# mixer_board_input_and_mute_circuit.net
KiCad netlist of a schematic drawn in EAGLE
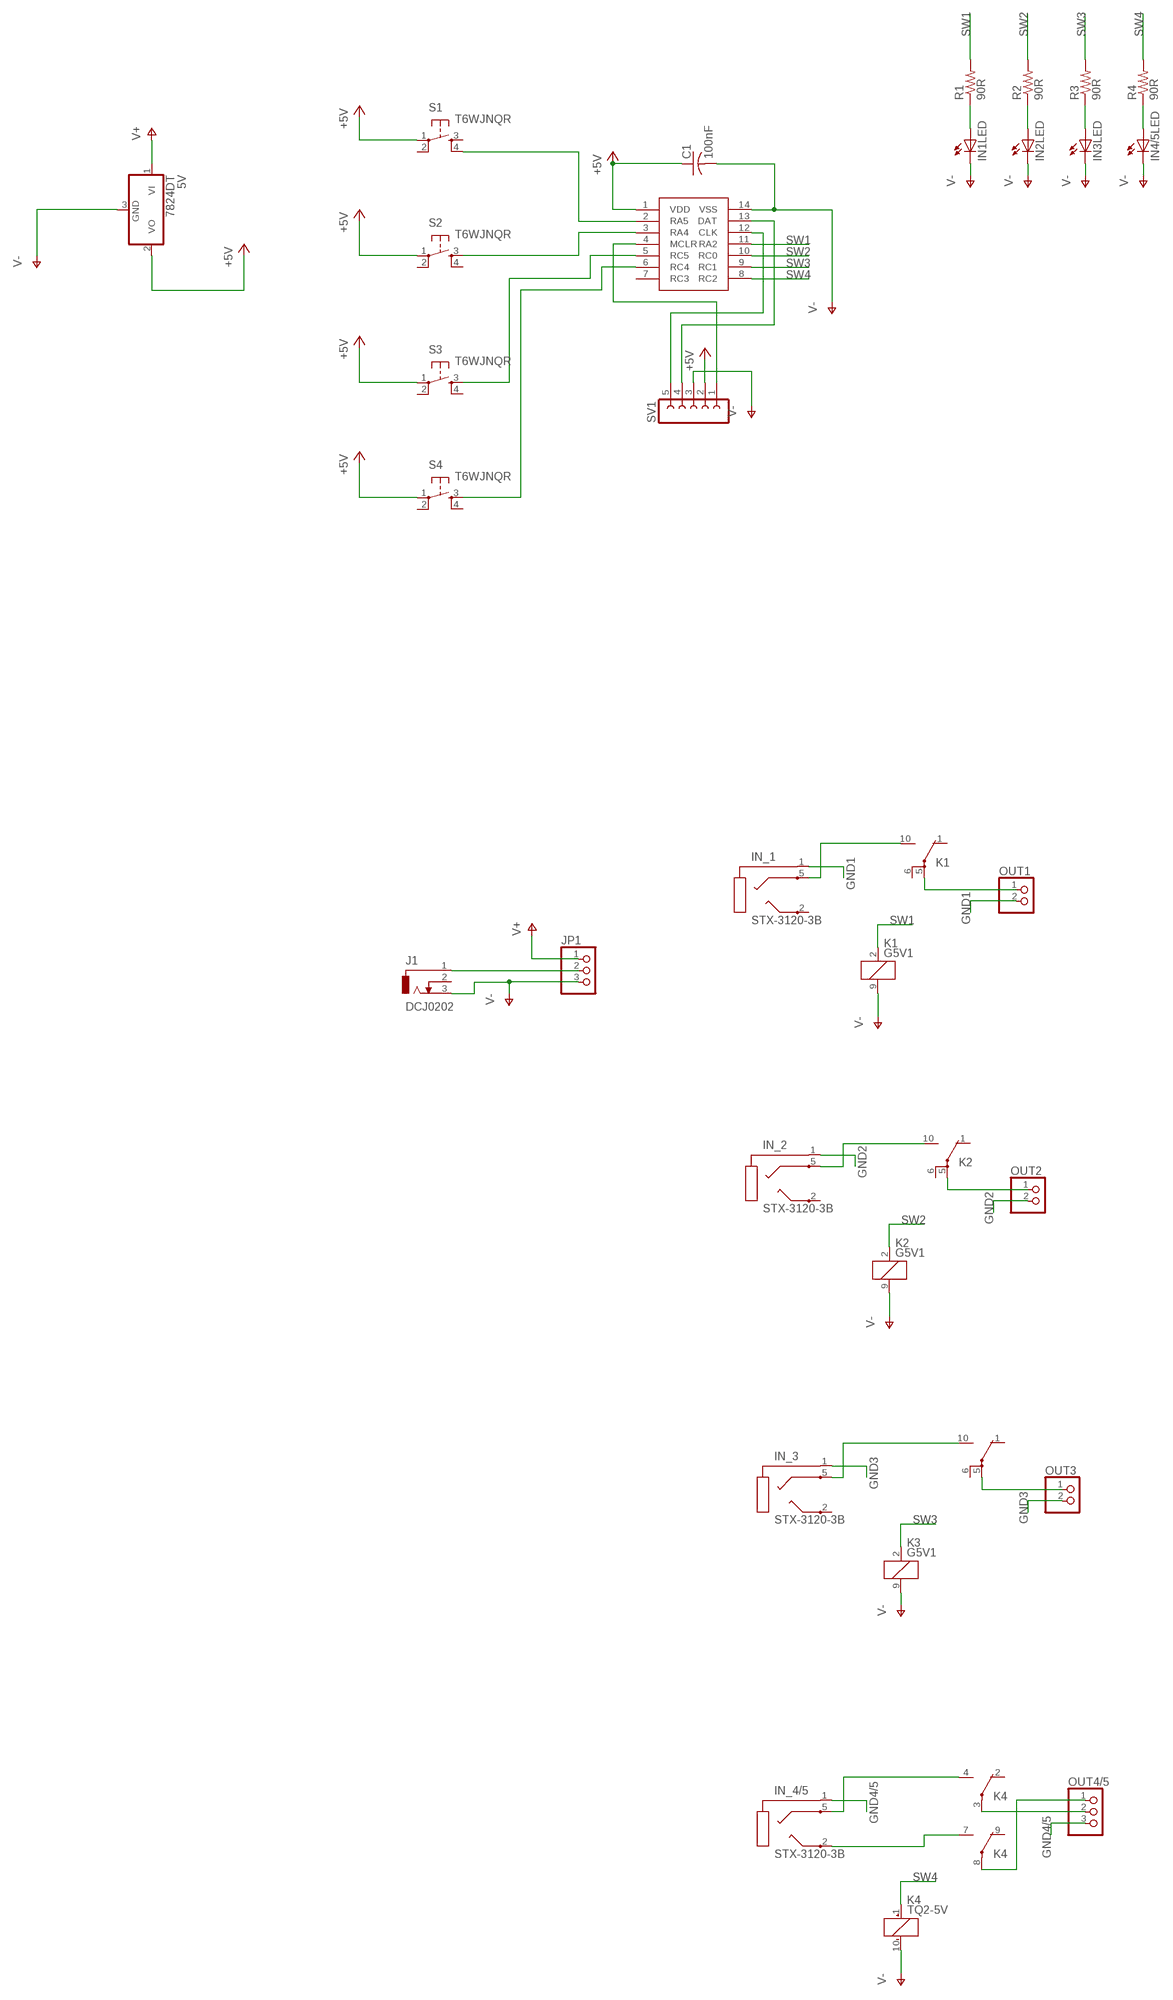
[diagram p0: schematic, sheet 1]

(export (version "E")
  (design (tool "Eeschema 10.0.6"))
  (components
    (comp (ref "5V")
      (value "7824DT")
      (footprint "eagle-import:TO252")
      (libsource (lib "eagle-import") (part "78DT24"))
    )
    (comp (ref "C1")
      (value "100nF")
      (footprint "eagle-import:C0805")
      (libsource (lib "eagle-import") (part "C-USC0805"))
    )
    (comp (ref "IN1LED")
      (value "LEDCHIPLED_1206")
      (footprint "eagle-import:CHIPLED_1206")
      (libsource (lib "eagle-import") (part "LEDCHIPLED_1206"))
    )
    (comp (ref "IN2LED")
      (value "LEDCHIPLED_1206")
      (footprint "eagle-import:CHIPLED_1206")
      (libsource (lib "eagle-import") (part "LEDCHIPLED_1206"))
    )
    (comp (ref "IN3LED")
      (value "LEDCHIPLED_1206")
      (footprint "eagle-import:CHIPLED_1206")
      (libsource (lib "eagle-import") (part "LEDCHIPLED_1206"))
    )
    (comp (ref "IN4/5LED")
      (value "LEDCHIPLED_1206")
      (footprint "eagle-import:CHIPLED_1206")
      (libsource (lib "eagle-import") (part "LEDCHIPLED_1206"))
    )
    (comp (ref "IN_1")
      (value "STX-3120-3B")
      (footprint "eagle-import:STX-3120")
      (libsource (lib "eagle-import") (part "STX-3120-3B"))
    )
    (comp (ref "IN_2")
      (value "STX-3120-3B")
      (footprint "eagle-import:STX-3120")
      (libsource (lib "eagle-import") (part "STX-3120-3B"))
    )
    (comp (ref "IN_3")
      (value "STX-3120-3B")
      (footprint "eagle-import:STX-3120")
      (libsource (lib "eagle-import") (part "STX-3120-3B"))
    )
    (comp (ref "IN_4/5")
      (value "STX-3120-3B")
      (footprint "eagle-import:STX-3120")
      (libsource (lib "eagle-import") (part "STX-3120-3B"))
    )
    (comp (ref "J1")
      (value "DCJ0202")
      (footprint "eagle-import:DCJ0202")
      (libsource (lib "eagle-import") (part "DCJ0202"))
    )
    (comp (ref "JP1")
      (value "PINHD-1X3/90")
      (footprint "eagle-import:1X03_90")
      (libsource (lib "eagle-import") (part "PINHD-1X3/90"))
    )
    (comp (ref "K1")
      (value "G5V1")
      (footprint "eagle-import:G5V1")
      (fields (field (name "MPN") "G5V-1-DC24"))
      (libsource (lib "eagle-import") (part "G5V1"))
    )
    (comp (ref "K2")
      (value "G5V1")
      (footprint "eagle-import:G5V1")
      (fields (field (name "MPN") "G5V-1-DC24"))
      (libsource (lib "eagle-import") (part "G5V1"))
    )
    (comp (ref "K3")
      (value "G5V1")
      (footprint "eagle-import:G5V1")
      (fields (field (name "MPN") "G5V-1-DC24"))
      (libsource (lib "eagle-import") (part "G5V1"))
    )
    (comp (ref "K4")
      (value "TQ2-5V")
      (footprint "eagle-import:TQ2")
      (fields (field (name "MF") "AROMAT/ MATSUSHITA"))
      (libsource (lib "eagle-import") (part "TQ2?-5V"))
    )
    (comp (ref "OUT1")
      (value "PINHD-1X2/90")
      (footprint "eagle-import:1X02_90")
      (libsource (lib "eagle-import") (part "PINHD-1X2/90"))
    )
    (comp (ref "OUT2")
      (value "PINHD-1X2/90")
      (footprint "eagle-import:1X02_90")
      (libsource (lib "eagle-import") (part "PINHD-1X2/90"))
    )
    (comp (ref "OUT3")
      (value "PINHD-1X2/90")
      (footprint "eagle-import:1X02_90")
      (libsource (lib "eagle-import") (part "PINHD-1X2/90"))
    )
    (comp (ref "OUT4/5")
      (value "PINHD-1X3/90")
      (footprint "eagle-import:1X03_90")
      (libsource (lib "eagle-import") (part "PINHD-1X3/90"))
    )
    (comp (ref "R1")
      (value "90R")
      (footprint "eagle-import:M0805")
      (libsource (lib "eagle-import") (part "R-US_M0805"))
    )
    (comp (ref "R2")
      (value "90R")
      (footprint "eagle-import:M0805")
      (libsource (lib "eagle-import") (part "R-US_M0805"))
    )
    (comp (ref "R3")
      (value "90R")
      (footprint "eagle-import:M0805")
      (libsource (lib "eagle-import") (part "R-US_M0805"))
    )
    (comp (ref "R4")
      (value "90R")
      (footprint "eagle-import:M0805")
      (libsource (lib "eagle-import") (part "R-US_M0805"))
    )
    (comp (ref "S1")
      (value "T6WJNQR")
      (footprint "eagle-import:T6WJ2NGQR")
      (libsource (lib "eagle-import") (part "T6WJNQR"))
    )
    (comp (ref "S2")
      (value "T6WJNQR")
      (footprint "eagle-import:T6WJ2NGQR")
      (libsource (lib "eagle-import") (part "T6WJNQR"))
    )
    (comp (ref "S3")
      (value "T6WJNQR")
      (footprint "eagle-import:T6WJ2NGQR")
      (libsource (lib "eagle-import") (part "T6WJNQR"))
    )
    (comp (ref "S4")
      (value "T6WJNQR")
      (footprint "eagle-import:T6WJ2NGQR")
      (libsource (lib "eagle-import") (part "T6WJNQR"))
    )
    (comp (ref "SV1")
      (value "FE05-1")
      (footprint "eagle-import:FE05-1")
      (libsource (lib "eagle-import") (part "FE05-1"))
    )
    (comp (ref "U1")
      (value "PIC16F18426")
      (footprint "eagle-import:SO14")
      (libsource (lib "eagle-import") (part "PIC16F18426"))
    )
  )
  (nets
    (net (code "1") (name "+5V") (class "Default")
      (node (ref "5V") (pin "2") (pinfunction "VO_2") (pintype "passive"))
      (node (ref "C1") (pin "1") (pinfunction "1_1") (pintype "passive"))
      (node (ref "S1") (pin "1") (pinfunction "1_1") (pintype "passive"))
      (node (ref "S2") (pin "1") (pinfunction "1_1") (pintype "passive"))
      (node (ref "S3") (pin "1") (pinfunction "1_1") (pintype "passive"))
      (node (ref "S4") (pin "1") (pinfunction "1_1") (pintype "passive"))
      (node (ref "SV1") (pin "2") (pinfunction "2_2") (pintype "passive"))
      (node (ref "U1") (pin "1") (pinfunction "VDD_1") (pintype "bidirectional"))
    )
    (net (code "2") (name "/GND1") (class "Default")
      (node (ref "IN_1") (pin "1") (pinfunction "1_1") (pintype "passive"))
      (node (ref "OUT1") (pin "2") (pinfunction "2_2") (pintype "passive"))
    )
    (net (code "3") (name "/GND2") (class "Default")
      (node (ref "IN_2") (pin "1") (pinfunction "1_1") (pintype "passive"))
      (node (ref "OUT2") (pin "2") (pinfunction "2_2") (pintype "passive"))
    )
    (net (code "4") (name "/GND3") (class "Default")
      (node (ref "IN_3") (pin "1") (pinfunction "1_1") (pintype "passive"))
      (node (ref "OUT3") (pin "2") (pinfunction "2_2") (pintype "passive"))
    )
    (net (code "5") (name "/GND4{slash}5") (class "Default")
      (node (ref "IN_4/5") (pin "1") (pinfunction "1_1") (pintype "passive"))
      (node (ref "OUT4/5") (pin "3") (pinfunction "3_3") (pintype "passive"))
    )
    (net (code "6") (name "/SW1") (class "Default")
      (node (ref "K1") (pin "2") (pinfunction "1_2") (pintype "passive"))
      (node (ref "R1") (pin "2") (pinfunction "2_2") (pintype "passive"))
      (node (ref "U1") (pin "11") (pinfunction "RA2_11") (pintype "bidirectional"))
    )
    (net (code "7") (name "/SW2") (class "Default")
      (node (ref "K2") (pin "2") (pinfunction "1_2") (pintype "passive"))
      (node (ref "R2") (pin "2") (pinfunction "2_2") (pintype "passive"))
      (node (ref "U1") (pin "10") (pinfunction "RC0_10") (pintype "bidirectional"))
    )
    (net (code "8") (name "/SW3") (class "Default")
      (node (ref "K3") (pin "2") (pinfunction "1_2") (pintype "passive"))
      (node (ref "R3") (pin "2") (pinfunction "2_2") (pintype "passive"))
      (node (ref "U1") (pin "9") (pinfunction "RC1_9") (pintype "bidirectional"))
    )
    (net (code "9") (name "/SW4") (class "Default")
      (node (ref "K4") (pin "1") (pinfunction "+_1") (pintype "passive"))
      (node (ref "R4") (pin "2") (pinfunction "2_2") (pintype "passive"))
      (node (ref "U1") (pin "8") (pinfunction "RC2_8") (pintype "bidirectional"))
    )
    (net (code "10") (name "Net-(IN1LED-PadA)") (class "Default")
      (node (ref "IN1LED") (pin "A") (pinfunction "A_A") (pintype "passive"))
      (node (ref "R1") (pin "1") (pinfunction "1_1") (pintype "passive"))
    )
    (net (code "11") (name "Net-(IN2LED-PadA)") (class "Default")
      (node (ref "IN2LED") (pin "A") (pinfunction "A_A") (pintype "passive"))
      (node (ref "R2") (pin "1") (pinfunction "1_1") (pintype "passive"))
    )
    (net (code "12") (name "Net-(IN3LED-PadA)") (class "Default")
      (node (ref "IN3LED") (pin "A") (pinfunction "A_A") (pintype "passive"))
      (node (ref "R3") (pin "1") (pinfunction "1_1") (pintype "passive"))
    )
    (net (code "13") (name "Net-(IN4/5LED-PadA)") (class "Default")
      (node (ref "IN4/5LED") (pin "A") (pinfunction "A_A") (pintype "passive"))
      (node (ref "R4") (pin "1") (pinfunction "1_1") (pintype "passive"))
    )
    (net (code "14") (name "Net-(J1-Pad1)") (class "Default")
      (node (ref "J1") (pin "1") (pinfunction "1_1") (pintype "passive"))
      (node (ref "JP1") (pin "2") (pinfunction "2_2") (pintype "passive"))
    )
    (net (code "15") (name "Net-(K1B-P-Pad5)") (class "Default")
      (node (ref "K1") (pin "5") (pinfunction "P_5") (pintype "passive"))
      (node (ref "OUT1") (pin "1") (pinfunction "1_1") (pintype "passive"))
    )
    (net (code "16") (name "Net-(K1B-S)") (class "Default")
      (node (ref "IN_1") (pin "5") (pinfunction "5_5") (pintype "passive"))
      (node (ref "K1") (pin "10") (pinfunction "S_10") (pintype "passive"))
    )
    (net (code "17") (name "Net-(K2B-P-Pad5)") (class "Default")
      (node (ref "K2") (pin "5") (pinfunction "P_5") (pintype "passive"))
      (node (ref "OUT2") (pin "1") (pinfunction "1_1") (pintype "passive"))
    )
    (net (code "18") (name "Net-(K2B-S)") (class "Default")
      (node (ref "IN_2") (pin "5") (pinfunction "5_5") (pintype "passive"))
      (node (ref "K2") (pin "10") (pinfunction "S_10") (pintype "passive"))
    )
    (net (code "19") (name "Net-(K3B-P-Pad5)") (class "Default")
      (node (ref "K3") (pin "5") (pinfunction "P_5") (pintype "passive"))
      (node (ref "OUT3") (pin "1") (pinfunction "1_1") (pintype "passive"))
    )
    (net (code "20") (name "Net-(K3B-S)") (class "Default")
      (node (ref "IN_3") (pin "5") (pinfunction "5_5") (pintype "passive"))
      (node (ref "K3") (pin "10") (pinfunction "S_10") (pintype "passive"))
    )
    (net (code "21") (name "Net-(K4A-P)") (class "Default")
      (node (ref "K4") (pin "3") (pinfunction "P_3") (pintype "passive"))
      (node (ref "OUT4/5") (pin "2") (pinfunction "2_2") (pintype "passive"))
    )
    (net (code "22") (name "Net-(K4A-S)") (class "Default")
      (node (ref "IN_4/5") (pin "5") (pinfunction "5_5") (pintype "passive"))
      (node (ref "K4") (pin "4") (pinfunction "S_4") (pintype "passive"))
    )
    (net (code "23") (name "Net-(K4B-P)") (class "Default")
      (node (ref "K4") (pin "8") (pinfunction "P_8") (pintype "passive"))
      (node (ref "OUT4/5") (pin "1") (pinfunction "1_1") (pintype "passive"))
    )
    (net (code "24") (name "Net-(K4B-S)") (class "Default")
      (node (ref "IN_4/5") (pin "2") (pinfunction "2_2") (pintype "passive"))
      (node (ref "K4") (pin "7") (pinfunction "S_7") (pintype "passive"))
    )
    (net (code "25") (name "Net-(U1-CLK)") (class "Default")
      (node (ref "SV1") (pin "5") (pinfunction "5_5") (pintype "passive"))
      (node (ref "U1") (pin "12") (pinfunction "CLK_12") (pintype "bidirectional"))
    )
    (net (code "26") (name "Net-(U1-DAT)") (class "Default")
      (node (ref "SV1") (pin "4") (pinfunction "4_4") (pintype "passive"))
      (node (ref "U1") (pin "13") (pinfunction "DAT_13") (pintype "bidirectional"))
    )
    (net (code "27") (name "Net-(U1-MCLR)") (class "Default")
      (node (ref "SV1") (pin "1") (pinfunction "1_1") (pintype "passive"))
      (node (ref "U1") (pin "4") (pinfunction "MCLR_4") (pintype "bidirectional"))
    )
    (net (code "28") (name "Net-(U1-RA4)") (class "Default")
      (node (ref "S2") (pin "3") (pinfunction "3_3") (pintype "passive"))
      (node (ref "U1") (pin "3") (pinfunction "RA4_3") (pintype "bidirectional"))
    )
    (net (code "29") (name "Net-(U1-RA5)") (class "Default")
      (node (ref "S1") (pin "4") (pinfunction "4_4") (pintype "passive"))
      (node (ref "U1") (pin "2") (pinfunction "RA5_2") (pintype "bidirectional"))
    )
    (net (code "30") (name "Net-(U1-RC4)") (class "Default")
      (node (ref "S4") (pin "3") (pinfunction "3_3") (pintype "passive"))
      (node (ref "U1") (pin "6") (pinfunction "RC4_6") (pintype "bidirectional"))
    )
    (net (code "31") (name "Net-(U1-RC5)") (class "Default")
      (node (ref "S3") (pin "3") (pinfunction "3_3") (pintype "passive"))
      (node (ref "U1") (pin "5") (pinfunction "RC5_5") (pintype "bidirectional"))
    )
    (net (code "32") (name "V+") (class "Default")
      (node (ref "5V") (pin "1") (pinfunction "VI_1") (pintype "input"))
      (node (ref "JP1") (pin "1") (pinfunction "1_1") (pintype "passive"))
    )
    (net (code "33") (name "V-") (class "Default")
      (node (ref "5V") (pin "3") (pinfunction "GND_3") (pintype "passive"))
      (node (ref "C1") (pin "2") (pinfunction "2_2") (pintype "passive"))
      (node (ref "IN1LED") (pin "C") (pinfunction "C_C") (pintype "passive"))
      (node (ref "IN2LED") (pin "C") (pinfunction "C_C") (pintype "passive"))
      (node (ref "IN3LED") (pin "C") (pinfunction "C_C") (pintype "passive"))
      (node (ref "IN4/5LED") (pin "C") (pinfunction "C_C") (pintype "passive"))
      (node (ref "J1") (pin "3") (pinfunction "3_3") (pintype "passive"))
      (node (ref "JP1") (pin "3") (pinfunction "3_3") (pintype "passive"))
      (node (ref "K1") (pin "9") (pinfunction "2_9") (pintype "passive"))
      (node (ref "K2") (pin "9") (pinfunction "2_9") (pintype "passive"))
      (node (ref "K3") (pin "9") (pinfunction "2_9") (pintype "passive"))
      (node (ref "K4") (pin "10") (pinfunction "-_10") (pintype "passive"))
      (node (ref "SV1") (pin "3") (pinfunction "3_3") (pintype "passive"))
      (node (ref "U1") (pin "14") (pinfunction "VSS_14") (pintype "bidirectional"))
    )
    (net (code "34") (name "unconnected-(IN_1-Pad2)") (class "Default")
      (node (ref "IN_1") (pin "2") (pinfunction "2_2") (pintype "passive"))
    )
    (net (code "35") (name "unconnected-(IN_2-Pad2)") (class "Default")
      (node (ref "IN_2") (pin "2") (pinfunction "2_2") (pintype "passive"))
    )
    (net (code "36") (name "unconnected-(IN_3-Pad2)") (class "Default")
      (node (ref "IN_3") (pin "2") (pinfunction "2_2") (pintype "passive"))
    )
    (net (code "37") (name "unconnected-(J1-Pad2)") (class "Default")
      (node (ref "J1") (pin "2") (pinfunction "2_2") (pintype "passive"))
    )
    (net (code "38") (name "unconnected-(K1B-O-Pad1)") (class "Default")
      (node (ref "K1") (pin "1") (pinfunction "O_1") (pintype "passive"))
    )
    (net (code "39") (name "unconnected-(K1B-P-Pad6)") (class "Default")
      (node (ref "K1") (pin "6") (pinfunction "P_6") (pintype "passive"))
    )
    (net (code "40") (name "unconnected-(K2B-O-Pad1)") (class "Default")
      (node (ref "K2") (pin "1") (pinfunction "O_1") (pintype "passive"))
    )
    (net (code "41") (name "unconnected-(K2B-P-Pad6)") (class "Default")
      (node (ref "K2") (pin "6") (pinfunction "P_6") (pintype "passive"))
    )
    (net (code "42") (name "unconnected-(K3B-O-Pad1)") (class "Default")
      (node (ref "K3") (pin "1") (pinfunction "O_1") (pintype "passive"))
    )
    (net (code "43") (name "unconnected-(K3B-P-Pad6)") (class "Default")
      (node (ref "K3") (pin "6") (pinfunction "P_6") (pintype "passive"))
    )
    (net (code "44") (name "unconnected-(K4A-O-Pad2)") (class "Default")
      (node (ref "K4") (pin "2") (pinfunction "O_2") (pintype "passive"))
    )
    (net (code "45") (name "unconnected-(K4B-O-Pad9)") (class "Default")
      (node (ref "K4") (pin "9") (pinfunction "O_9") (pintype "passive"))
    )
    (net (code "46") (name "unconnected-(S1-Pad2)") (class "Default")
      (node (ref "S1") (pin "2") (pinfunction "2_2") (pintype "passive"))
    )
    (net (code "47") (name "unconnected-(S1-Pad3)") (class "Default")
      (node (ref "S1") (pin "3") (pinfunction "3_3") (pintype "passive"))
    )
    (net (code "48") (name "unconnected-(S2-Pad2)") (class "Default")
      (node (ref "S2") (pin "2") (pinfunction "2_2") (pintype "passive"))
    )
    (net (code "49") (name "unconnected-(S2-Pad4)") (class "Default")
      (node (ref "S2") (pin "4") (pinfunction "4_4") (pintype "passive"))
    )
    (net (code "50") (name "unconnected-(S3-Pad2)") (class "Default")
      (node (ref "S3") (pin "2") (pinfunction "2_2") (pintype "passive"))
    )
    (net (code "51") (name "unconnected-(S3-Pad4)") (class "Default")
      (node (ref "S3") (pin "4") (pinfunction "4_4") (pintype "passive"))
    )
    (net (code "52") (name "unconnected-(S4-Pad2)") (class "Default")
      (node (ref "S4") (pin "2") (pinfunction "2_2") (pintype "passive"))
    )
    (net (code "53") (name "unconnected-(S4-Pad4)") (class "Default")
      (node (ref "S4") (pin "4") (pinfunction "4_4") (pintype "passive"))
    )
    (net (code "54") (name "unconnected-(U1-RC3-Pad7)") (class "Default")
      (node (ref "U1") (pin "7") (pinfunction "RC3_7") (pintype "bidirectional"))
    )
  )
)
